# ts808.net
KiCad netlist of a schematic drawn in EAGLE
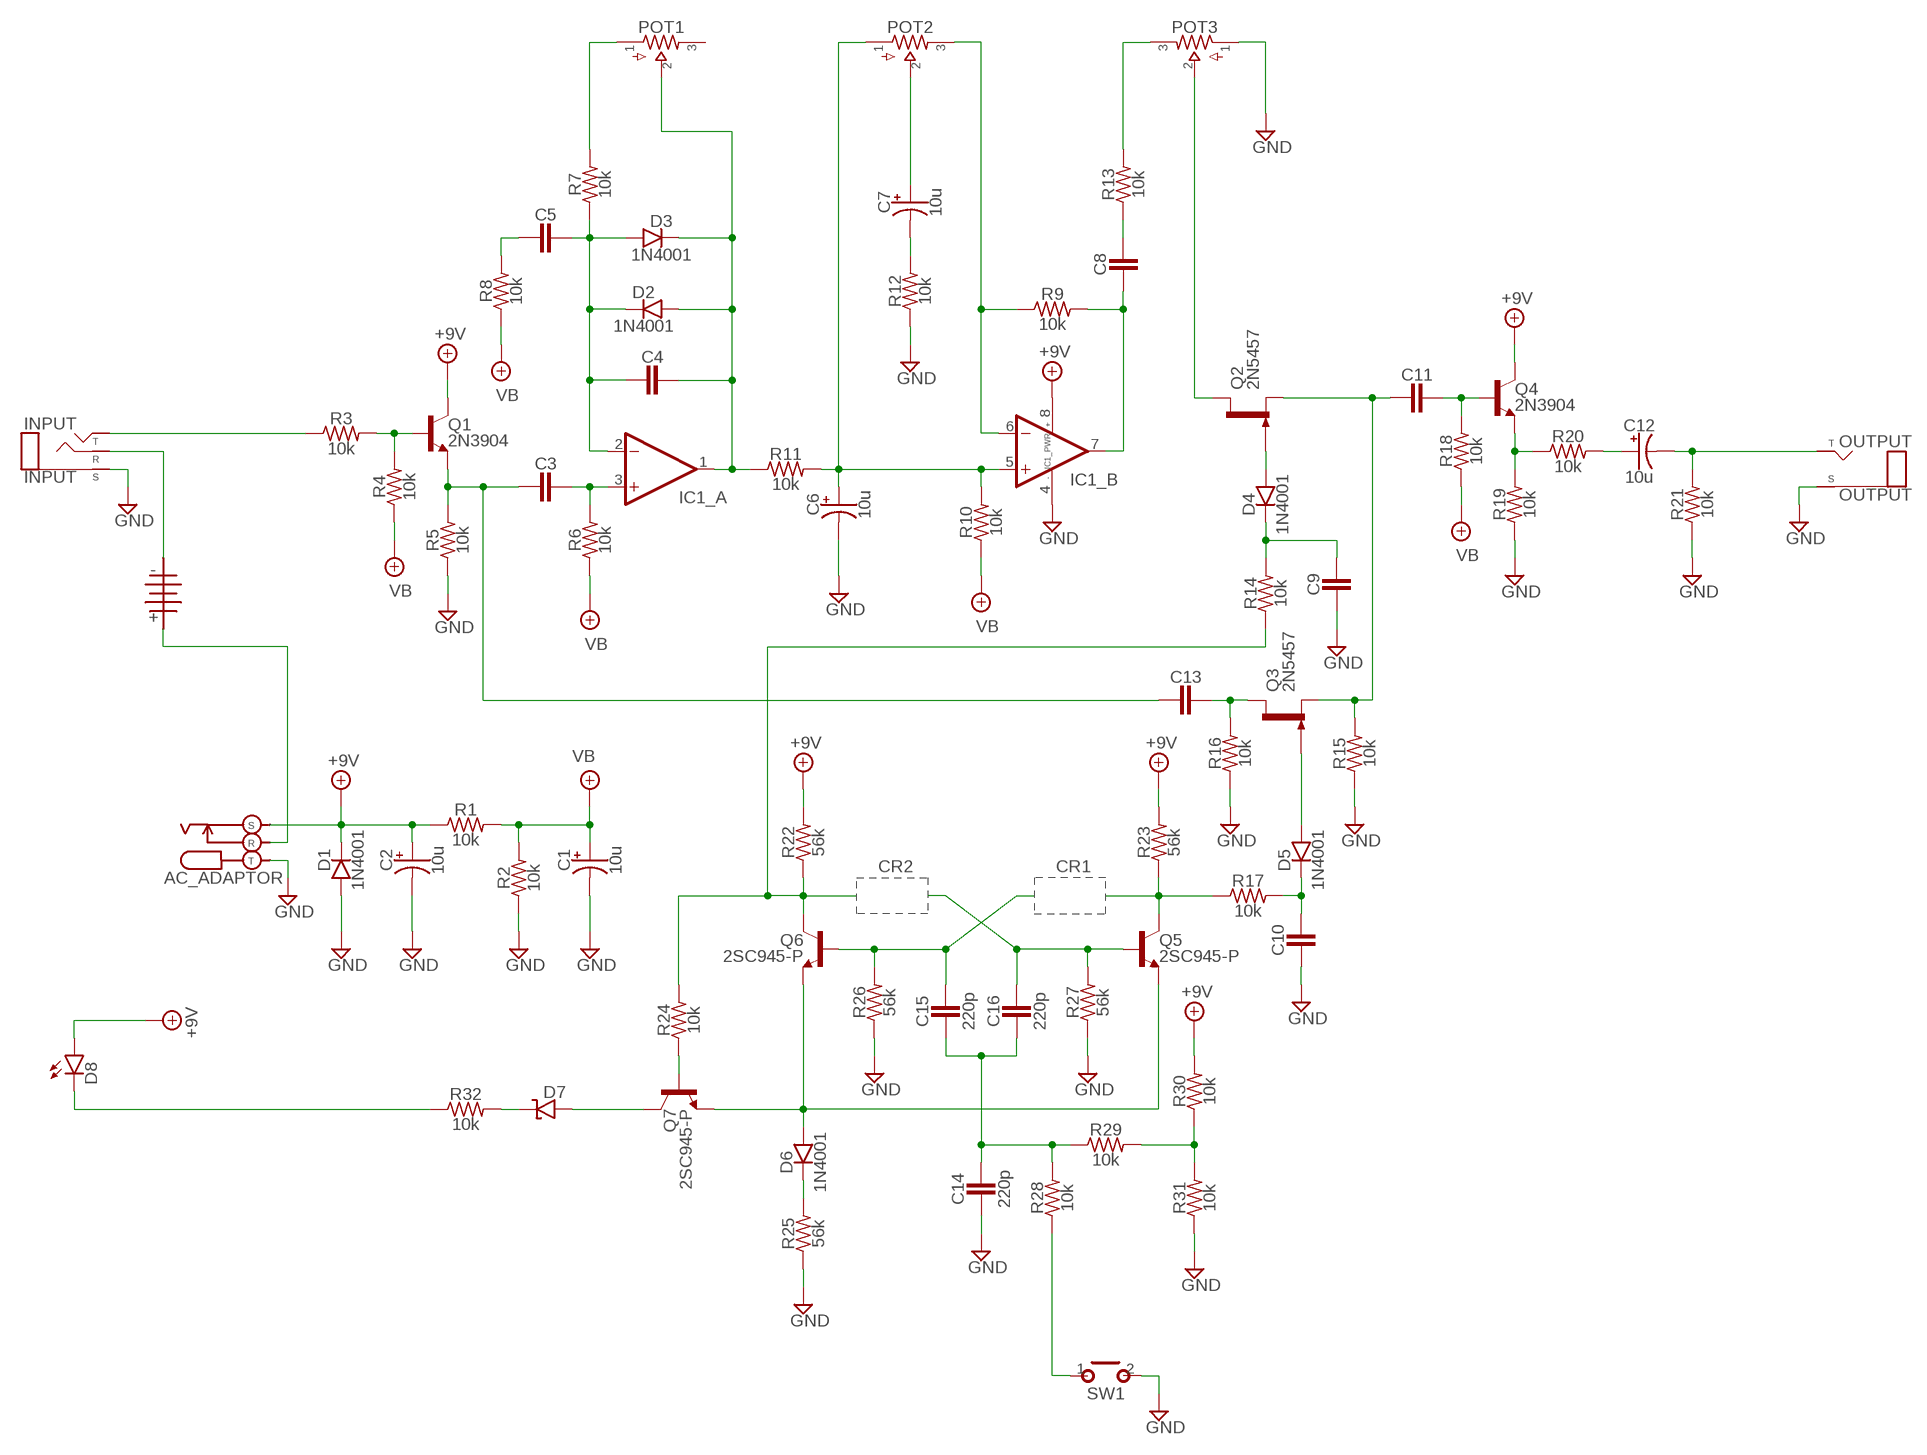
[diagram p0: schematic, sheet 1]

(export (version "E")
  (design (tool "Eeschema 10.0.6"))
  (components
    (comp (ref "AC_ADAPTOR")
      (value "DCJACK")
      (footprint "eagle-import:DC_KOBICONN")
      (libsource (lib "eagle-import") (part "DC_KOBICONN"))
    )
    (comp (ref "BATTERY")
      (value "BATTERY")
      (footprint "eagle-import:TWO_PADS")
      (libsource (lib "eagle-import") (part "BATTERY"))
    )
    (comp (ref "C1")
      (value "10u")
      (footprint "eagle-import:050_020")
      (libsource (lib "eagle-import") (part "0500"))
    )
    (comp (ref "C2")
      (value "10u")
      (footprint "eagle-import:050_020")
      (libsource (lib "eagle-import") (part "0500"))
    )
    (comp (ref "C3")
      (value "CER/FILMBOX.1")
      (footprint "eagle-import:BOX_SMALL")
      (libsource (lib "eagle-import") (part "CER/FILMBOX.1"))
    )
    (comp (ref "C4")
      (value "CER/FILMBOX.1")
      (footprint "eagle-import:BOX_SMALL")
      (libsource (lib "eagle-import") (part "CER/FILMBOX.1"))
    )
    (comp (ref "C5")
      (value "CER/FILMBOX.1")
      (footprint "eagle-import:BOX_SMALL")
      (libsource (lib "eagle-import") (part "CER/FILMBOX.1"))
    )
    (comp (ref "C6")
      (value "10u")
      (footprint "eagle-import:050_020")
      (libsource (lib "eagle-import") (part "0500"))
    )
    (comp (ref "C7")
      (value "10u")
      (footprint "eagle-import:050_020")
      (libsource (lib "eagle-import") (part "0500"))
    )
    (comp (ref "C8")
      (value "CER/FILMBOX.1")
      (footprint "eagle-import:BOX_SMALL")
      (libsource (lib "eagle-import") (part "CER/FILMBOX.1"))
    )
    (comp (ref "C9")
      (value "CER/FILMBOX.1")
      (footprint "eagle-import:BOX_SMALL")
      (libsource (lib "eagle-import") (part "CER/FILMBOX.1"))
    )
    (comp (ref "C10")
      (value "CER/FILMBOX.1")
      (footprint "eagle-import:BOX_SMALL")
      (libsource (lib "eagle-import") (part "CER/FILMBOX.1"))
    )
    (comp (ref "C11")
      (value "CER/FILMBOX.1")
      (footprint "eagle-import:BOX_SMALL")
      (libsource (lib "eagle-import") (part "CER/FILMBOX.1"))
    )
    (comp (ref "C12")
      (value "10u")
      (footprint "eagle-import:050_020")
      (libsource (lib "eagle-import") (part "0500"))
    )
    (comp (ref "C13")
      (value "CER/FILMBOX.1")
      (footprint "eagle-import:BOX_SMALL")
      (libsource (lib "eagle-import") (part "CER/FILMBOX.1"))
    )
    (comp (ref "C14")
      (value "220p")
      (footprint "eagle-import:BOX_SMALL")
      (libsource (lib "eagle-import") (part "CER/FILMBOX.1"))
    )
    (comp (ref "C15")
      (value "220p")
      (footprint "eagle-import:BOX_SMALL")
      (libsource (lib "eagle-import") (part "CER/FILMBOX.1"))
    )
    (comp (ref "C16")
      (value "220p")
      (footprint "eagle-import:BOX_SMALL")
      (libsource (lib "eagle-import") (part "CER/FILMBOX.1"))
    )
    (comp (ref "D1")
      (value "1N4001")
      (footprint "eagle-import:DO35-2")
      (libsource (lib "eagle-import") (part "DO35.2"))
    )
    (comp (ref "D2")
      (value "1N4001")
      (footprint "eagle-import:DO35-2")
      (libsource (lib "eagle-import") (part "DO35.2"))
    )
    (comp (ref "D3")
      (value "1N4001")
      (footprint "eagle-import:DO35-2")
      (libsource (lib "eagle-import") (part "DO35.2"))
    )
    (comp (ref "D4")
      (value "1N4001")
      (footprint "eagle-import:DO35-2")
      (libsource (lib "eagle-import") (part "DO35.2"))
    )
    (comp (ref "D5")
      (value "1N4001")
      (footprint "eagle-import:DO35-2")
      (libsource (lib "eagle-import") (part "DO35.2"))
    )
    (comp (ref "D6")
      (value "1N4001")
      (footprint "eagle-import:DO35-2")
      (libsource (lib "eagle-import") (part "DO35.2"))
    )
    (comp (ref "D7")
      (value "ZENER.2")
      (footprint "eagle-import:DO41-2")
      (libsource (lib "eagle-import") (part "ZENER.2"))
    )
    (comp (ref "D8")
      (value "LED")
      (footprint "eagle-import:3MM_D")
      (libsource (lib "eagle-import") (part "LED"))
    )
    (comp (ref "IC1")
      (value "DUALTH")
      (footprint "eagle-import:DIL0")
      (libsource (lib "eagle-import") (part "DUALTH"))
    )
    (comp (ref "INPUT")
      (value "INPUT")
      (footprint "eagle-import:THREEPADS")
      (libsource (lib "eagle-import") (part "STEREO3PADS"))
    )
    (comp (ref "OUTPUT")
      (value "OUTPUT")
      (footprint "eagle-import:TWO_PADS")
      (libsource (lib "eagle-import") (part "MONO"))
    )
    (comp (ref "POT1")
      (value "POTS16MM")
      (footprint "eagle-import:16MM")
      (libsource (lib "eagle-import") (part "POTS16MM"))
    )
    (comp (ref "POT2")
      (value "POTS16MM")
      (footprint "eagle-import:16MM")
      (libsource (lib "eagle-import") (part "POTS16MM"))
    )
    (comp (ref "POT3")
      (value "POTS16MM")
      (footprint "eagle-import:16MM")
      (libsource (lib "eagle-import") (part "POTS16MM"))
    )
    (comp (ref "Q1")
      (value "2N3904")
      (footprint "eagle-import:TO92-")
      (libsource (lib "eagle-import") (part "2N3904"))
    )
    (comp (ref "Q2")
      (value "2N5457")
      (footprint "eagle-import:TO92-")
      (libsource (lib "eagle-import") (part "2N5457"))
    )
    (comp (ref "Q3")
      (value "2N5457")
      (footprint "eagle-import:TO92-")
      (libsource (lib "eagle-import") (part "2N5457"))
    )
    (comp (ref "Q4")
      (value "2N3904")
      (footprint "eagle-import:TO92-")
      (libsource (lib "eagle-import") (part "2N3904"))
    )
    (comp (ref "Q5")
      (value "2SC945-P")
      (footprint "eagle-import:TO92-")
      (libsource (lib "eagle-import") (part "2SC828A"))
    )
    (comp (ref "Q6")
      (value "2SC945-P")
      (footprint "eagle-import:TO92-")
      (libsource (lib "eagle-import") (part "2SC828A"))
    )
    (comp (ref "Q7")
      (value "2SC945-P")
      (footprint "eagle-import:TO92-")
      (libsource (lib "eagle-import") (part "2SC828A"))
    )
    (comp (ref "R1")
      (value "10k")
      (footprint "eagle-import:R0207_3")
      (libsource (lib "eagle-import") (part "R_.3B"))
    )
    (comp (ref "R2")
      (value "10k")
      (footprint "eagle-import:R0207_3")
      (libsource (lib "eagle-import") (part "R_.3B"))
    )
    (comp (ref "R3")
      (value "10k")
      (footprint "eagle-import:R0207_3")
      (libsource (lib "eagle-import") (part "R_.3B"))
    )
    (comp (ref "R4")
      (value "10k")
      (footprint "eagle-import:R0207_3")
      (libsource (lib "eagle-import") (part "R_.3B"))
    )
    (comp (ref "R5")
      (value "10k")
      (footprint "eagle-import:R0207_3")
      (libsource (lib "eagle-import") (part "R_.3B"))
    )
    (comp (ref "R6")
      (value "10k")
      (footprint "eagle-import:R0207_3")
      (libsource (lib "eagle-import") (part "R_.3B"))
    )
    (comp (ref "R7")
      (value "10k")
      (footprint "eagle-import:R0207_3")
      (libsource (lib "eagle-import") (part "R_.3B"))
    )
    (comp (ref "R8")
      (value "10k")
      (footprint "eagle-import:R0207_3")
      (libsource (lib "eagle-import") (part "R_.3B"))
    )
    (comp (ref "R9")
      (value "10k")
      (footprint "eagle-import:R0207_3")
      (libsource (lib "eagle-import") (part "R_.3B"))
    )
    (comp (ref "R10")
      (value "10k")
      (footprint "eagle-import:R0207_3")
      (libsource (lib "eagle-import") (part "R_.3B"))
    )
    (comp (ref "R11")
      (value "10k")
      (footprint "eagle-import:R0207_3")
      (libsource (lib "eagle-import") (part "R_.3B"))
    )
    (comp (ref "R12")
      (value "10k")
      (footprint "eagle-import:R0207_3")
      (libsource (lib "eagle-import") (part "R_.3B"))
    )
    (comp (ref "R13")
      (value "10k")
      (footprint "eagle-import:R0207_3")
      (libsource (lib "eagle-import") (part "R_.3B"))
    )
    (comp (ref "R14")
      (value "10k")
      (footprint "eagle-import:R0207_3")
      (libsource (lib "eagle-import") (part "R_.3B"))
    )
    (comp (ref "R15")
      (value "10k")
      (footprint "eagle-import:R0207_3")
      (libsource (lib "eagle-import") (part "R_.3B"))
    )
    (comp (ref "R16")
      (value "10k")
      (footprint "eagle-import:R0207_3")
      (libsource (lib "eagle-import") (part "R_.3B"))
    )
    (comp (ref "R17")
      (value "10k")
      (footprint "eagle-import:R0207_3")
      (libsource (lib "eagle-import") (part "R_.3B"))
    )
    (comp (ref "R18")
      (value "10k")
      (footprint "eagle-import:R0207_3")
      (libsource (lib "eagle-import") (part "R_.3B"))
    )
    (comp (ref "R19")
      (value "10k")
      (footprint "eagle-import:R0207_3")
      (libsource (lib "eagle-import") (part "R_.3B"))
    )
    (comp (ref "R20")
      (value "10k")
      (footprint "eagle-import:R0207_3")
      (libsource (lib "eagle-import") (part "R_.3B"))
    )
    (comp (ref "R21")
      (value "10k")
      (footprint "eagle-import:R0207_3")
      (libsource (lib "eagle-import") (part "R_.3B"))
    )
    (comp (ref "R22")
      (value "56k")
      (footprint "eagle-import:R0207_3")
      (libsource (lib "eagle-import") (part "R_.3B"))
    )
    (comp (ref "R23")
      (value "56k")
      (footprint "eagle-import:R0207_3")
      (libsource (lib "eagle-import") (part "R_.3B"))
    )
    (comp (ref "R24")
      (value "10k")
      (footprint "eagle-import:R0207_3")
      (libsource (lib "eagle-import") (part "R_.3B"))
    )
    (comp (ref "R25")
      (value "56k")
      (footprint "eagle-import:R0207_3")
      (libsource (lib "eagle-import") (part "R_.3B"))
    )
    (comp (ref "R26")
      (value "56k")
      (footprint "eagle-import:R0207_3")
      (libsource (lib "eagle-import") (part "R_.3B"))
    )
    (comp (ref "R27")
      (value "56k")
      (footprint "eagle-import:R0207_3")
      (libsource (lib "eagle-import") (part "R_.3B"))
    )
    (comp (ref "R28")
      (value "10k")
      (footprint "eagle-import:R0207_3")
      (libsource (lib "eagle-import") (part "R_.3B"))
    )
    (comp (ref "R29")
      (value "10k")
      (footprint "eagle-import:R0207_3")
      (libsource (lib "eagle-import") (part "R_.3B"))
    )
    (comp (ref "R30")
      (value "10k")
      (footprint "eagle-import:R0207_3")
      (libsource (lib "eagle-import") (part "R_.3B"))
    )
    (comp (ref "R31")
      (value "10k")
      (footprint "eagle-import:R0207_3")
      (libsource (lib "eagle-import") (part "R_.3B"))
    )
    (comp (ref "R32")
      (value "10k")
      (footprint "eagle-import:R0207_3")
      (libsource (lib "eagle-import") (part "R_.3B"))
    )
    (comp (ref "SW1")
      (value "MOMENTARY")
      (footprint "eagle-import:SPST")
      (libsource (lib "eagle-import") (part "MOMENTARY"))
    )
  )
  (nets
    (net (code "1") (name "+9V") (class "Default")
      (node (ref "AC_ADAPTOR") (pin "S") (pinfunction "S_S") (pintype "bidirectional"))
      (node (ref "C2") (pin "+") (pinfunction "+_+") (pintype "passive"))
      (node (ref "D1") (pin "C") (pinfunction "C_C") (pintype "passive"))
      (node (ref "D8") (pin "ANODE") (pinfunction "A_ANODE") (pintype "passive"))
      (node (ref "IC1") (pin "8") (pinfunction "V+_8") (pintype "power_in"))
      (node (ref "Q1") (pin "1") (pinfunction "C_1") (pintype "passive"))
      (node (ref "Q4") (pin "1") (pinfunction "C_1") (pintype "passive"))
      (node (ref "R1") (pin "1") (pinfunction "1_1") (pintype "passive"))
      (node (ref "R22") (pin "2") (pinfunction "2_2") (pintype "passive"))
      (node (ref "R23") (pin "2") (pinfunction "2_2") (pintype "passive"))
      (node (ref "R30") (pin "2") (pinfunction "2_2") (pintype "passive"))
    )
    (net (code "2") (name "GND") (class "Default")
      (node (ref "AC_ADAPTOR") (pin "T") (pinfunction "T_T") (pintype "bidirectional"))
      (node (ref "C1") (pin "-") (pinfunction "-_-") (pintype "passive"))
      (node (ref "C10") (pin "2") (pinfunction "2_2") (pintype "passive"))
      (node (ref "C14") (pin "2") (pinfunction "2_2") (pintype "passive"))
      (node (ref "C2") (pin "-") (pinfunction "-_-") (pintype "passive"))
      (node (ref "C6") (pin "-") (pinfunction "-_-") (pintype "passive"))
      (node (ref "C9") (pin "2") (pinfunction "2_2") (pintype "passive"))
      (node (ref "D1") (pin "A") (pinfunction "A_A") (pintype "passive"))
      (node (ref "IC1") (pin "4") (pinfunction "V-_4") (pintype "power_in"))
      (node (ref "INPUT") (pin "SLEEVE") (pinfunction "S_SLEEVE") (pintype "passive"))
      (node (ref "OUTPUT") (pin "S") (pinfunction "SLEEVE_S") (pintype "passive"))
      (node (ref "POT3") (pin "1") (pinfunction "1_1") (pintype "passive"))
      (node (ref "R12") (pin "1") (pinfunction "1_1") (pintype "passive"))
      (node (ref "R15") (pin "1") (pinfunction "1_1") (pintype "passive"))
      (node (ref "R16") (pin "1") (pinfunction "1_1") (pintype "passive"))
      (node (ref "R19") (pin "1") (pinfunction "1_1") (pintype "passive"))
      (node (ref "R2") (pin "1") (pinfunction "1_1") (pintype "passive"))
      (node (ref "R21") (pin "1") (pinfunction "1_1") (pintype "passive"))
      (node (ref "R25") (pin "1") (pinfunction "1_1") (pintype "passive"))
      (node (ref "R26") (pin "1") (pinfunction "1_1") (pintype "passive"))
      (node (ref "R27") (pin "1") (pinfunction "1_1") (pintype "passive"))
      (node (ref "R31") (pin "1") (pinfunction "1_1") (pintype "passive"))
      (node (ref "R5") (pin "1") (pinfunction "1_1") (pintype "passive"))
      (node (ref "SW1") (pin "2") (pinfunction "S_2") (pintype "passive"))
    )
    (net (code "3") (name "Net-(BATTERY-P$1)") (class "Default")
      (node (ref "AC_ADAPTOR") (pin "R") (pinfunction "R_R") (pintype "bidirectional"))
      (node (ref "BATTERY") (pin "T") (pinfunction "P$1_T") (pintype "bidirectional"))
    )
    (net (code "4") (name "Net-(BATTERY-P$2)") (class "Default")
      (node (ref "BATTERY") (pin "S") (pinfunction "P$2_S") (pintype "bidirectional"))
      (node (ref "INPUT") (pin "RING") (pinfunction "R_RING") (pintype "passive"))
    )
    (net (code "5") (name "Net-(C5-Pad2)") (class "Default")
      (node (ref "C5") (pin "2") (pinfunction "2_2") (pintype "passive"))
      (node (ref "R8") (pin "2") (pinfunction "2_2") (pintype "passive"))
    )
    (net (code "6") (name "Net-(C7-Pad+)") (class "Default")
      (node (ref "C7") (pin "+") (pinfunction "+_+") (pintype "passive"))
      (node (ref "POT2") (pin "2") (pinfunction "2_2") (pintype "passive"))
    )
    (net (code "7") (name "Net-(C7-Pad-)") (class "Default")
      (node (ref "C7") (pin "-") (pinfunction "-_-") (pintype "passive"))
      (node (ref "R12") (pin "2") (pinfunction "2_2") (pintype "passive"))
    )
    (net (code "8") (name "Net-(C8-Pad1)") (class "Default")
      (node (ref "C8") (pin "1") (pinfunction "1_1") (pintype "passive"))
      (node (ref "R13") (pin "1") (pinfunction "1_1") (pintype "passive"))
    )
    (net (code "9") (name "Net-(C9-Pad1)") (class "Default")
      (node (ref "C9") (pin "1") (pinfunction "1_1") (pintype "passive"))
      (node (ref "D4") (pin "C") (pinfunction "C_C") (pintype "passive"))
      (node (ref "R14") (pin "2") (pinfunction "2_2") (pintype "passive"))
    )
    (net (code "10") (name "Net-(C10-Pad1)") (class "Default")
      (node (ref "C10") (pin "1") (pinfunction "1_1") (pintype "passive"))
      (node (ref "D5") (pin "C") (pinfunction "C_C") (pintype "passive"))
      (node (ref "R17") (pin "2") (pinfunction "2_2") (pintype "passive"))
    )
    (net (code "11") (name "Net-(C12-Pad+)") (class "Default")
      (node (ref "C12") (pin "+") (pinfunction "+_+") (pintype "passive"))
      (node (ref "R20") (pin "2") (pinfunction "2_2") (pintype "passive"))
    )
    (net (code "12") (name "Net-(C14-Pad1)") (class "Default")
      (node (ref "C14") (pin "1") (pinfunction "1_1") (pintype "passive"))
      (node (ref "C15") (pin "2") (pinfunction "2_2") (pintype "passive"))
      (node (ref "C16") (pin "2") (pinfunction "2_2") (pintype "passive"))
      (node (ref "R28") (pin "2") (pinfunction "2_2") (pintype "passive"))
      (node (ref "R29") (pin "1") (pinfunction "1_1") (pintype "passive"))
    )
    (net (code "13") (name "Net-(D6-PadC)") (class "Default")
      (node (ref "D6") (pin "C") (pinfunction "C_C") (pintype "passive"))
      (node (ref "R25") (pin "2") (pinfunction "2_2") (pintype "passive"))
    )
    (net (code "14") (name "Net-(D7-PadC)") (class "Default")
      (node (ref "D7") (pin "C") (pinfunction "C_C") (pintype "passive"))
      (node (ref "R32") (pin "2") (pinfunction "2_2") (pintype "passive"))
    )
    (net (code "15") (name "Net-(D8-C)") (class "Default")
      (node (ref "D8") (pin "P$1") (pinfunction "C_P$1") (pintype "passive"))
      (node (ref "R32") (pin "1") (pinfunction "1_1") (pintype "passive"))
    )
    (net (code "16") (name "Net-(IC1A-+IN)") (class "Default")
      (node (ref "C3") (pin "1") (pinfunction "1_1") (pintype "passive"))
      (node (ref "IC1") (pin "3") (pinfunction "+IN_3") (pintype "input"))
      (node (ref "R6") (pin "2") (pinfunction "2_2") (pintype "passive"))
    )
    (net (code "17") (name "Net-(IC1A--IN)") (class "Default")
      (node (ref "C4") (pin "2") (pinfunction "2_2") (pintype "passive"))
      (node (ref "C5") (pin "1") (pinfunction "1_1") (pintype "passive"))
      (node (ref "D2") (pin "C") (pinfunction "C_C") (pintype "passive"))
      (node (ref "D3") (pin "A") (pinfunction "A_A") (pintype "passive"))
      (node (ref "IC1") (pin "2") (pinfunction "-IN_2") (pintype "input"))
      (node (ref "R7") (pin "1") (pinfunction "1_1") (pintype "passive"))
    )
    (net (code "18") (name "Net-(IC1A-OUT)") (class "Default")
      (node (ref "C4") (pin "1") (pinfunction "1_1") (pintype "passive"))
      (node (ref "D2") (pin "A") (pinfunction "A_A") (pintype "passive"))
      (node (ref "D3") (pin "C") (pinfunction "C_C") (pintype "passive"))
      (node (ref "IC1") (pin "1") (pinfunction "OUT_1") (pintype "output"))
      (node (ref "POT1") (pin "2") (pinfunction "2_2") (pintype "passive"))
      (node (ref "R11") (pin "1") (pinfunction "1_1") (pintype "passive"))
    )
    (net (code "19") (name "Net-(IC1B-+IN)") (class "Default")
      (node (ref "C6") (pin "+") (pinfunction "+_+") (pintype "passive"))
      (node (ref "IC1") (pin "5") (pinfunction "+IN_5") (pintype "input"))
      (node (ref "POT2") (pin "1") (pinfunction "1_1") (pintype "passive"))
      (node (ref "R10") (pin "2") (pinfunction "2_2") (pintype "passive"))
      (node (ref "R11") (pin "2") (pinfunction "2_2") (pintype "passive"))
    )
    (net (code "20") (name "Net-(IC1B--IN)") (class "Default")
      (node (ref "IC1") (pin "6") (pinfunction "-IN_6") (pintype "input"))
      (node (ref "POT2") (pin "3") (pinfunction "3_3") (pintype "passive"))
      (node (ref "R9") (pin "1") (pinfunction "1_1") (pintype "passive"))
    )
    (net (code "21") (name "Net-(IC1B-OUT)") (class "Default")
      (node (ref "C8") (pin "2") (pinfunction "2_2") (pintype "passive"))
      (node (ref "IC1") (pin "7") (pinfunction "OUT_7") (pintype "output"))
      (node (ref "R9") (pin "2") (pinfunction "2_2") (pintype "passive"))
    )
    (net (code "22") (name "Net-(INPUT-T)") (class "Default")
      (node (ref "INPUT") (pin "TIP") (pinfunction "T_TIP") (pintype "passive"))
      (node (ref "R3") (pin "1") (pinfunction "1_1") (pintype "passive"))
    )
    (net (code "23") (name "Net-(OUTPUT-TIP)") (class "Default")
      (node (ref "C12") (pin "-") (pinfunction "-_-") (pintype "passive"))
      (node (ref "OUTPUT") (pin "T") (pinfunction "TIP_T") (pintype "passive"))
      (node (ref "R21") (pin "2") (pinfunction "2_2") (pintype "passive"))
    )
    (net (code "24") (name "Net-(POT1-Pad1)") (class "Default")
      (node (ref "POT1") (pin "1") (pinfunction "1_1") (pintype "passive"))
      (node (ref "R7") (pin "2") (pinfunction "2_2") (pintype "passive"))
    )
    (net (code "25") (name "Net-(POT3-Pad3)") (class "Default")
      (node (ref "POT3") (pin "3") (pinfunction "3_3") (pintype "passive"))
      (node (ref "R13") (pin "2") (pinfunction "2_2") (pintype "passive"))
    )
    (net (code "26") (name "Net-(Q1-B)") (class "Default")
      (node (ref "Q1") (pin "2") (pinfunction "B_2") (pintype "passive"))
      (node (ref "R3") (pin "2") (pinfunction "2_2") (pintype "passive"))
      (node (ref "R4") (pin "2") (pinfunction "2_2") (pintype "passive"))
    )
    (net (code "27") (name "Net-(Q1-E)") (class "Default")
      (node (ref "C13") (pin "2") (pinfunction "2_2") (pintype "passive"))
      (node (ref "C3") (pin "2") (pinfunction "2_2") (pintype "passive"))
      (node (ref "Q1") (pin "3") (pinfunction "E_3") (pintype "passive"))
      (node (ref "R5") (pin "2") (pinfunction "2_2") (pintype "passive"))
    )
    (net (code "28") (name "Net-(Q2-D)") (class "Default")
      (node (ref "POT3") (pin "2") (pinfunction "2_2") (pintype "passive"))
      (node (ref "Q2") (pin "3") (pinfunction "D_3") (pintype "passive"))
    )
    (net (code "29") (name "Net-(Q2-G)") (class "Default")
      (node (ref "D4") (pin "A") (pinfunction "A_A") (pintype "passive"))
      (node (ref "Q2") (pin "1") (pinfunction "G_1") (pintype "passive"))
    )
    (net (code "30") (name "Net-(Q2-S)") (class "Default")
      (node (ref "C11") (pin "2") (pinfunction "2_2") (pintype "passive"))
      (node (ref "Q2") (pin "2") (pinfunction "S_2") (pintype "passive"))
      (node (ref "Q3") (pin "2") (pinfunction "S_2") (pintype "passive"))
      (node (ref "R15") (pin "2") (pinfunction "2_2") (pintype "passive"))
    )
    (net (code "31") (name "Net-(Q3-D)") (class "Default")
      (node (ref "C13") (pin "1") (pinfunction "1_1") (pintype "passive"))
      (node (ref "Q3") (pin "3") (pinfunction "D_3") (pintype "passive"))
      (node (ref "R16") (pin "2") (pinfunction "2_2") (pintype "passive"))
    )
    (net (code "32") (name "Net-(Q3-G)") (class "Default")
      (node (ref "D5") (pin "A") (pinfunction "A_A") (pintype "passive"))
      (node (ref "Q3") (pin "1") (pinfunction "G_1") (pintype "passive"))
    )
    (net (code "33") (name "Net-(Q4-B)") (class "Default")
      (node (ref "C11") (pin "1") (pinfunction "1_1") (pintype "passive"))
      (node (ref "Q4") (pin "2") (pinfunction "B_2") (pintype "passive"))
      (node (ref "R18") (pin "2") (pinfunction "2_2") (pintype "passive"))
    )
    (net (code "34") (name "Net-(Q4-E)") (class "Default")
      (node (ref "Q4") (pin "3") (pinfunction "E_3") (pintype "passive"))
      (node (ref "R19") (pin "2") (pinfunction "2_2") (pintype "passive"))
      (node (ref "R20") (pin "1") (pinfunction "1_1") (pintype "passive"))
    )
    (net (code "35") (name "Net-(Q5-B)") (class "Default")
      (node (ref "C16") (pin "1") (pinfunction "1_1") (pintype "passive"))
      (node (ref "Q5") (pin "1") (pinfunction "B_1") (pintype "passive"))
      (node (ref "R27") (pin "2") (pinfunction "2_2") (pintype "passive"))
    )
    (net (code "36") (name "Net-(Q5-C)") (class "Default")
      (node (ref "Q5") (pin "2") (pinfunction "C_2") (pintype "passive"))
      (node (ref "R17") (pin "1") (pinfunction "1_1") (pintype "passive"))
      (node (ref "R23") (pin "1") (pinfunction "1_1") (pintype "passive"))
    )
    (net (code "37") (name "Net-(Q5-E)") (class "Default")
      (node (ref "D6") (pin "A") (pinfunction "A_A") (pintype "passive"))
      (node (ref "Q5") (pin "3") (pinfunction "E_3") (pintype "passive"))
      (node (ref "Q6") (pin "3") (pinfunction "E_3") (pintype "passive"))
      (node (ref "Q7") (pin "3") (pinfunction "E_3") (pintype "passive"))
    )
    (net (code "38") (name "Net-(Q6-B)") (class "Default")
      (node (ref "C15") (pin "1") (pinfunction "1_1") (pintype "passive"))
      (node (ref "Q6") (pin "1") (pinfunction "B_1") (pintype "passive"))
      (node (ref "R26") (pin "2") (pinfunction "2_2") (pintype "passive"))
    )
    (net (code "39") (name "Net-(Q6-C)") (class "Default")
      (node (ref "Q6") (pin "2") (pinfunction "C_2") (pintype "passive"))
      (node (ref "R14") (pin "1") (pinfunction "1_1") (pintype "passive"))
      (node (ref "R22") (pin "1") (pinfunction "1_1") (pintype "passive"))
      (node (ref "R24") (pin "2") (pinfunction "2_2") (pintype "passive"))
    )
    (net (code "40") (name "Net-(Q7-B)") (class "Default")
      (node (ref "Q7") (pin "1") (pinfunction "B_1") (pintype "passive"))
      (node (ref "R24") (pin "1") (pinfunction "1_1") (pintype "passive"))
    )
    (net (code "41") (name "Net-(Q7-C)") (class "Default")
      (node (ref "D7") (pin "A") (pinfunction "A_A") (pintype "passive"))
      (node (ref "Q7") (pin "2") (pinfunction "C_2") (pintype "passive"))
    )
    (net (code "42") (name "Net-(R29-Pad2)") (class "Default")
      (node (ref "R29") (pin "2") (pinfunction "2_2") (pintype "passive"))
      (node (ref "R30") (pin "1") (pinfunction "1_1") (pintype "passive"))
      (node (ref "R31") (pin "2") (pinfunction "2_2") (pintype "passive"))
    )
    (net (code "43") (name "Net-(SW1-P)") (class "Default")
      (node (ref "R28") (pin "1") (pinfunction "1_1") (pintype "passive"))
      (node (ref "SW1") (pin "1") (pinfunction "P_1") (pintype "passive"))
    )
    (net (code "44") (name "VB") (class "Default")
      (node (ref "C1") (pin "+") (pinfunction "+_+") (pintype "passive"))
      (node (ref "R1") (pin "2") (pinfunction "2_2") (pintype "passive"))
      (node (ref "R10") (pin "1") (pinfunction "1_1") (pintype "passive"))
      (node (ref "R18") (pin "1") (pinfunction "1_1") (pintype "passive"))
      (node (ref "R2") (pin "2") (pinfunction "2_2") (pintype "passive"))
      (node (ref "R4") (pin "1") (pinfunction "1_1") (pintype "passive"))
      (node (ref "R6") (pin "1") (pinfunction "1_1") (pintype "passive"))
      (node (ref "R8") (pin "1") (pinfunction "1_1") (pintype "passive"))
    )
    (net (code "45") (name "unconnected-(POT1-Pad3)") (class "Default")
      (node (ref "POT1") (pin "3") (pinfunction "3_3") (pintype "passive"))
    )
  )
)
